# SparkFun_6DoF_LSM6DSV16X.net
KiCad netlist of a schematic drawn in EAGLE
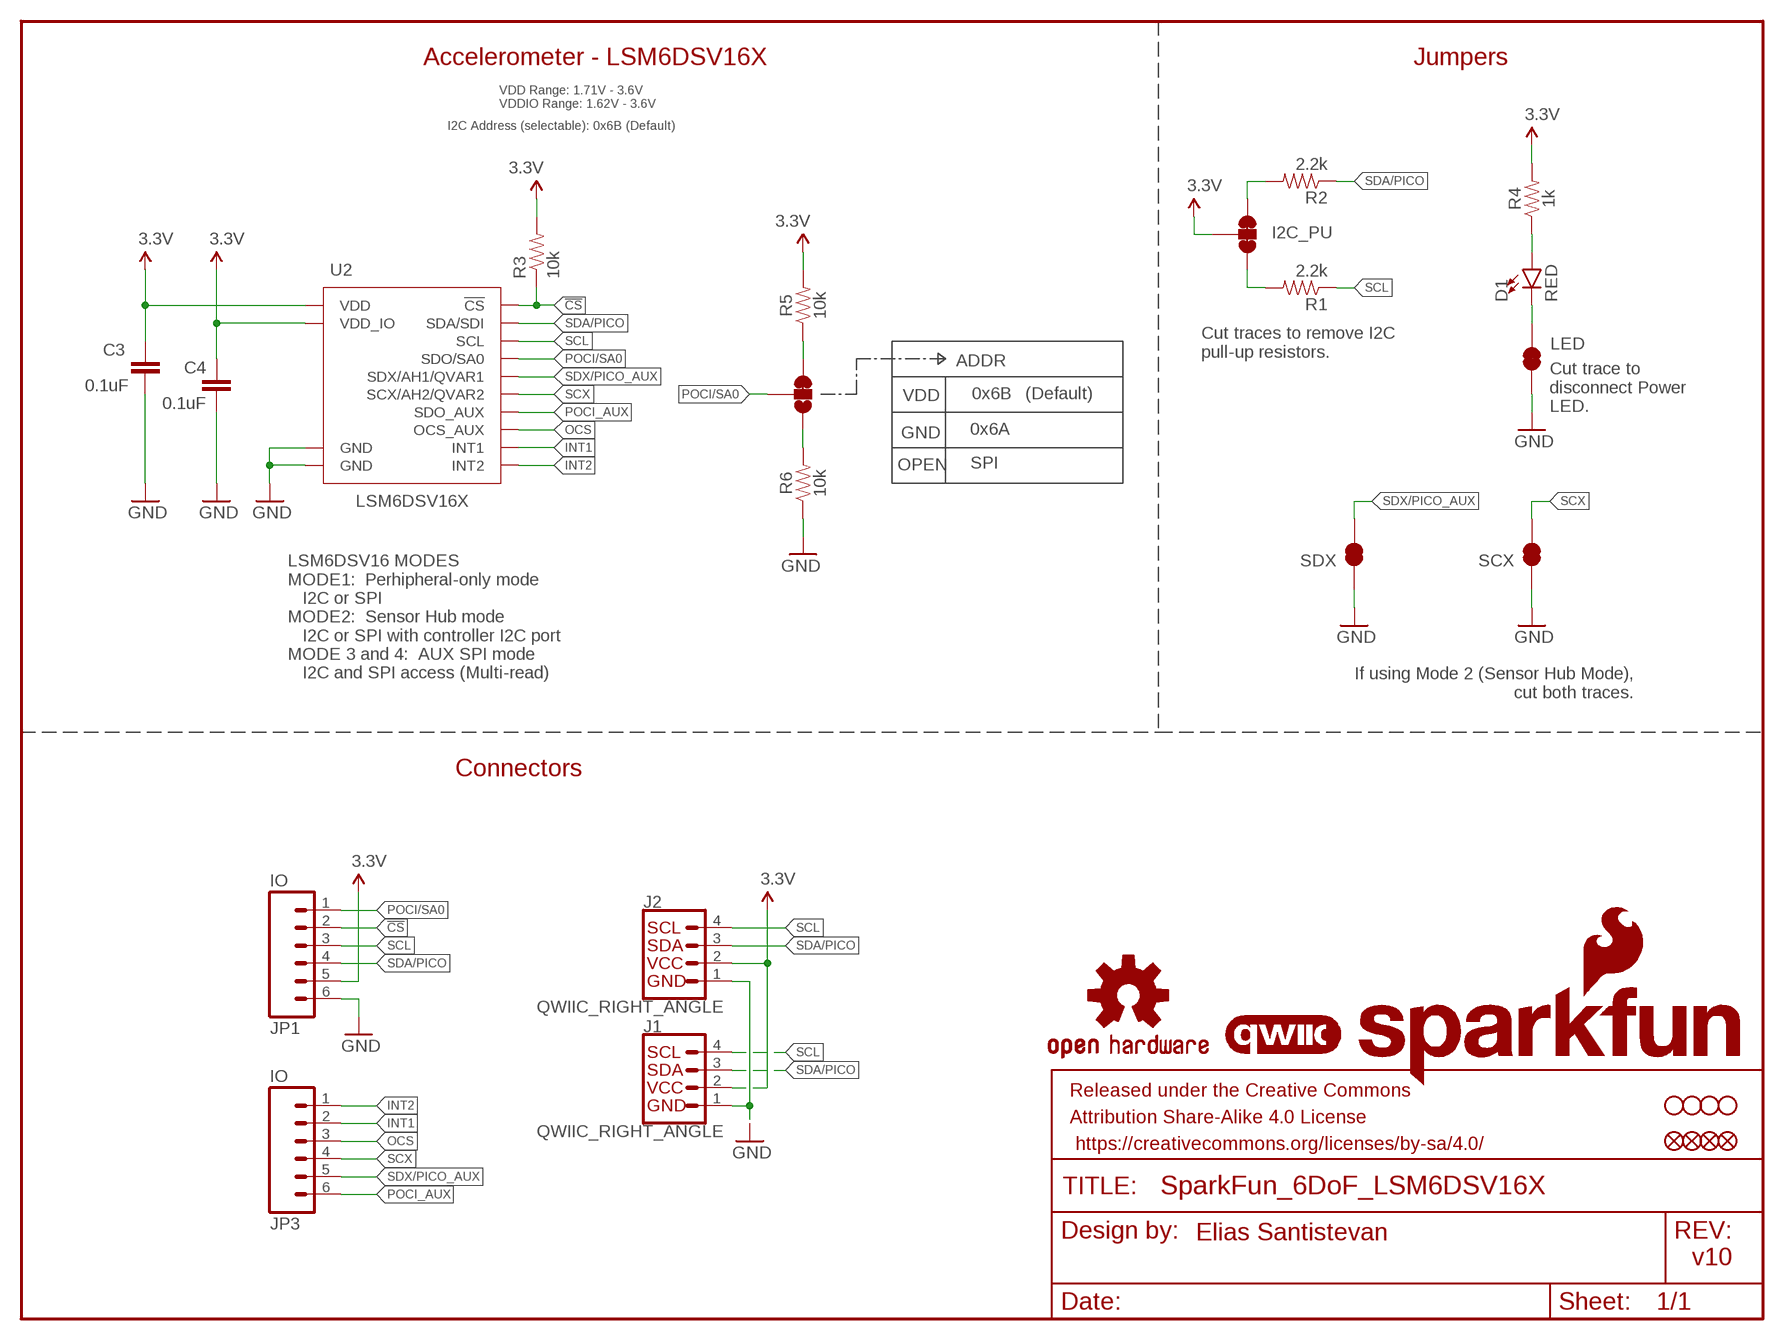
[diagram p0: schematic, sheet 1]

(export (version "E")
  (design (tool "Eeschema 10.0.6"))
  (components
    (comp (ref "ADDR")
      (value "JUMPER-SMT_3_1-NC_TRACE_SILK")
      (footprint "eagle-import:SMT-JUMPER_3_1-NC_TRACE_SILK")
      (libsource (lib "eagle-import") (part "JUMPER-SMT_3_1-NC_TRACE_SILK"))
    )
    (comp (ref "C3")
      (value "0.1uF")
      (footprint "eagle-import:0603")
      (libsource (lib "eagle-import") (part "0.1UF-0603-25V-(+80/-20%)"))
    )
    (comp (ref "C4")
      (value "0.1uF")
      (footprint "eagle-import:0603")
      (libsource (lib "eagle-import") (part "0.1UF-0603-25V-(+80/-20%)"))
    )
    (comp (ref "D1")
      (value "RED")
      (footprint "eagle-import:LED-0603")
      (libsource (lib "eagle-import") (part "LED-RED0603"))
    )
    (comp (ref "FD1")
      (value "FIDUCIALUFIDUCIAL")
      (footprint "eagle-import:FIDUCIAL-MICRO")
      (libsource (lib "eagle-import") (part "FIDUCIALUFIDUCIAL"))
    )
    (comp (ref "FD2")
      (value "FIDUCIALUFIDUCIAL")
      (footprint "eagle-import:FIDUCIAL-MICRO")
      (libsource (lib "eagle-import") (part "FIDUCIALUFIDUCIAL"))
    )
    (comp (ref "FID1")
      (value "FIDUCIALUFIDUCIAL")
      (footprint "eagle-import:FIDUCIAL-MICRO")
      (libsource (lib "eagle-import") (part "FIDUCIALUFIDUCIAL"))
    )
    (comp (ref "FID2")
      (value "FIDUCIALUFIDUCIAL")
      (footprint "eagle-import:FIDUCIAL-MICRO")
      (libsource (lib "eagle-import") (part "FIDUCIALUFIDUCIAL"))
    )
    (comp (ref "FRAME1")
      (value "FRAME-LETTER")
      (footprint "eagle-import:CREATIVE_COMMONS")
      (fields (field (name "DESIGNER") "Elias Santistevan"))
      (libsource (lib "eagle-import") (part "FRAME-LETTER"))
    )
    (comp (ref "I2C_PU")
      (value "S_MODE")
      (footprint "eagle-import:SMT-JUMPER_3_2-NC_TRACE_SILK")
      (libsource (lib "eagle-import") (part "JUMPER-SMT_3_2-NC_TRACE_SILK"))
    )
    (comp (ref "J1")
      (value "QWIIC_RIGHT_ANGLE")
      (footprint "eagle-import:JST04_1MM_RA")
      (libsource (lib "eagle-import") (part "QWIIC_CONNECTORJS-1MM"))
    )
    (comp (ref "J2")
      (value "QWIIC_RIGHT_ANGLE")
      (footprint "eagle-import:JST04_1MM_RA")
      (libsource (lib "eagle-import") (part "QWIIC_CONNECTORJS-1MM"))
    )
    (comp (ref "JP1")
      (value "IO")
      (footprint "eagle-import:1X06_NO_SILK")
      (libsource (lib "eagle-import") (part "CONN_06NO_SILK_NO_POP"))
    )
    (comp (ref "JP3")
      (value "IO")
      (footprint "eagle-import:1X06_NO_SILK")
      (libsource (lib "eagle-import") (part "CONN_06NO_SILK_NO_POP"))
    )
    (comp (ref "LED")
      (value "JUMPER-SMT_2_NC_TRACE_SILK")
      (footprint "eagle-import:SMT-JUMPER_2_NC_TRACE_SILK")
      (libsource (lib "eagle-import") (part "JUMPER-SMT_2_NC_TRACE_SILK"))
    )
    (comp (ref "LOGO1")
      (value "QWIIC_LOGO_4MM")
      (footprint "eagle-import:QWIIC_4MM")
      (libsource (lib "eagle-import") (part "QWIIC_LOGO_4MM"))
    )
    (comp (ref "LOGO2")
      (value "OSHW-LOGOMINI")
      (footprint "eagle-import:OSHW-LOGO-MINI")
      (libsource (lib "eagle-import") (part "OSHW-LOGOMINI"))
    )
    (comp (ref "LOGO3")
      (value "SFE_LOGO_NAME_FLAME.1_INCH")
      (footprint "eagle-import:SFE_LOGO_NAME_FLAME_.1")
      (libsource (lib "eagle-import") (part "SFE_LOGO_NAME_FLAME.1_INCH"))
    )
    (comp (ref "R1")
      (value "2.2k")
      (footprint "eagle-import:0603")
      (libsource (lib "eagle-import") (part "2.2KOHM-0603-1/10W-1%"))
    )
    (comp (ref "R2")
      (value "2.2k")
      (footprint "eagle-import:0603")
      (libsource (lib "eagle-import") (part "2.2KOHM-0603-1/10W-1%"))
    )
    (comp (ref "R3")
      (value "10k")
      (footprint "eagle-import:0603")
      (libsource (lib "eagle-import") (part "10KOHM-0603-1/10W-1%"))
    )
    (comp (ref "R4")
      (value "1k")
      (footprint "eagle-import:0603")
      (libsource (lib "eagle-import") (part "1KOHM-0603-1/10W-1%"))
    )
    (comp (ref "R5")
      (value "10k")
      (footprint "eagle-import:0603")
      (libsource (lib "eagle-import") (part "10KOHM-0603-1/10W-1%"))
    )
    (comp (ref "R6")
      (value "10k")
      (footprint "eagle-import:0603")
      (libsource (lib "eagle-import") (part "10KOHM-0603-1/10W-1%"))
    )
    (comp (ref "SCX")
      (value "JUMPER-SMT_2_NC_TRACE_SILK")
      (footprint "eagle-import:SMT-JUMPER_2_NC_TRACE_SILK")
      (libsource (lib "eagle-import") (part "JUMPER-SMT_2_NC_TRACE_SILK"))
    )
    (comp (ref "SDX")
      (value "JUMPER-SMT_2_NC_TRACE_SILK")
      (footprint "eagle-import:SMT-JUMPER_2_NC_TRACE_SILK")
      (libsource (lib "eagle-import") (part "JUMPER-SMT_2_NC_TRACE_SILK"))
    )
    (comp (ref "STANDOFF1")
      (value "STAND-OFFTIGHT")
      (footprint "eagle-import:STAND-OFF-TIGHT")
      (libsource (lib "eagle-import") (part "STAND-OFFTIGHT"))
    )
    (comp (ref "STANDOFF2")
      (value "STAND-OFFTIGHT")
      (footprint "eagle-import:STAND-OFF-TIGHT")
      (libsource (lib "eagle-import") (part "STAND-OFFTIGHT"))
    )
    (comp (ref "STANDOFF3")
      (value "STAND-OFFTIGHT")
      (footprint "eagle-import:STAND-OFF-TIGHT")
      (libsource (lib "eagle-import") (part "STAND-OFFTIGHT"))
    )
    (comp (ref "STANDOFF4")
      (value "STAND-OFFTIGHT")
      (footprint "eagle-import:STAND-OFF-TIGHT")
      (libsource (lib "eagle-import") (part "STAND-OFFTIGHT"))
    )
    (comp (ref "U2")
      (value "LSM6DSV16X")
      (footprint "eagle-import:LGA-14L")
      (libsource (lib "eagle-import") (part "LSM6DSV16X"))
    )
  )
  (nets
    (net (code "1") (name "/~{CS}") (class "Default")
      (node (ref "JP1") (pin "2") (pinfunction "2_2") (pintype "passive"))
      (node (ref "R3") (pin "1") (pinfunction "1_1") (pintype "passive"))
      (node (ref "U2") (pin "P12") (pinfunction "~{CS}_P12") (pintype "bidirectional"))
    )
    (net (code "2") (name "3.3V") (class "Default")
      (node (ref "C3") (pin "1") (pinfunction "1_1") (pintype "passive"))
      (node (ref "C4") (pin "1") (pinfunction "1_1") (pintype "passive"))
      (node (ref "I2C_PU") (pin "2") (pinfunction "2_2") (pintype "passive"))
      (node (ref "J1") (pin "2") (pinfunction "2_2") (pintype "power_in"))
      (node (ref "J2") (pin "2") (pinfunction "2_2") (pintype "power_in"))
      (node (ref "JP1") (pin "5") (pinfunction "5_5") (pintype "passive"))
      (node (ref "R3") (pin "2") (pinfunction "2_2") (pintype "passive"))
      (node (ref "R4") (pin "2") (pinfunction "2_2") (pintype "passive"))
      (node (ref "R5") (pin "2") (pinfunction "2_2") (pintype "passive"))
      (node (ref "U2") (pin "P5") (pinfunction "VDD_IO_P5") (pintype "power_in"))
      (node (ref "U2") (pin "P8") (pinfunction "VDD_P8") (pintype "power_in"))
    )
    (net (code "3") (name "GND") (class "Default")
      (node (ref "C3") (pin "2") (pinfunction "2_2") (pintype "passive"))
      (node (ref "C4") (pin "2") (pinfunction "2_2") (pintype "passive"))
      (node (ref "J1") (pin "1") (pinfunction "1_1") (pintype "power_in"))
      (node (ref "J2") (pin "1") (pinfunction "1_1") (pintype "power_in"))
      (node (ref "JP1") (pin "6") (pinfunction "6_6") (pintype "passive"))
      (node (ref "LED") (pin "1") (pinfunction "1_1") (pintype "passive"))
      (node (ref "R6") (pin "1") (pinfunction "1_1") (pintype "passive"))
      (node (ref "SCX") (pin "1") (pinfunction "1_1") (pintype "passive"))
      (node (ref "SDX") (pin "1") (pinfunction "1_1") (pintype "passive"))
      (node (ref "U2") (pin "P6") (pinfunction "GND_P6") (pintype "power_in"))
      (node (ref "U2") (pin "P7") (pinfunction "GND_P7") (pintype "power_in"))
    )
    (net (code "4") (name "INT1") (class "Default")
      (node (ref "JP3") (pin "2") (pinfunction "2_2") (pintype "passive"))
      (node (ref "U2") (pin "P4") (pinfunction "INT1_P4") (pintype "bidirectional"))
    )
    (net (code "5") (name "INT2") (class "Default")
      (node (ref "JP3") (pin "1") (pinfunction "1_1") (pintype "passive"))
      (node (ref "U2") (pin "P9") (pinfunction "INT2_P9") (pintype "bidirectional"))
    )
    (net (code "6") (name "Net-(ADDR-Pad1)") (class "Default")
      (node (ref "ADDR") (pin "1") (pinfunction "1_1") (pintype "passive"))
      (node (ref "R6") (pin "2") (pinfunction "2_2") (pintype "passive"))
    )
    (net (code "7") (name "Net-(ADDR-Pad3)") (class "Default")
      (node (ref "ADDR") (pin "3") (pinfunction "3_3") (pintype "passive"))
      (node (ref "R5") (pin "1") (pinfunction "1_1") (pintype "passive"))
    )
    (net (code "8") (name "Net-(D1-PadA)") (class "Default")
      (node (ref "D1") (pin "A") (pinfunction "A_A") (pintype "passive"))
      (node (ref "R4") (pin "1") (pinfunction "1_1") (pintype "passive"))
    )
    (net (code "9") (name "Net-(D1-PadC)") (class "Default")
      (node (ref "D1") (pin "C") (pinfunction "C_C") (pintype "passive"))
      (node (ref "LED") (pin "2") (pinfunction "2_2") (pintype "passive"))
    )
    (net (code "10") (name "Net-(I2C_PU-Pad1)") (class "Default")
      (node (ref "I2C_PU") (pin "1") (pinfunction "1_1") (pintype "passive"))
      (node (ref "R1") (pin "2") (pinfunction "2_2") (pintype "passive"))
    )
    (net (code "11") (name "Net-(I2C_PU-Pad3)") (class "Default")
      (node (ref "I2C_PU") (pin "3") (pinfunction "3_3") (pintype "passive"))
      (node (ref "R2") (pin "2") (pinfunction "2_2") (pintype "passive"))
    )
    (net (code "12") (name "OCS") (class "Default")
      (node (ref "JP3") (pin "3") (pinfunction "3_3") (pintype "passive"))
      (node (ref "U2") (pin "P10") (pinfunction "OCS_AUX_P10") (pintype "bidirectional"))
    )
    (net (code "13") (name "POCI_AUX") (class "Default")
      (node (ref "JP3") (pin "6") (pinfunction "6_6") (pintype "passive"))
      (node (ref "U2") (pin "P11") (pinfunction "SDO_AUX_P11") (pintype "bidirectional"))
    )
    (net (code "14") (name "POCI{slash}SA0") (class "Default")
      (node (ref "ADDR") (pin "2") (pinfunction "2_2") (pintype "passive"))
      (node (ref "JP1") (pin "1") (pinfunction "1_1") (pintype "passive"))
      (node (ref "U2") (pin "P1") (pinfunction "SDO/SA0_P1") (pintype "bidirectional"))
    )
    (net (code "15") (name "SCL") (class "Default")
      (node (ref "J1") (pin "4") (pinfunction "4_4") (pintype "passive"))
      (node (ref "J2") (pin "4") (pinfunction "4_4") (pintype "passive"))
      (node (ref "JP1") (pin "3") (pinfunction "3_3") (pintype "passive"))
      (node (ref "R1") (pin "1") (pinfunction "1_1") (pintype "passive"))
      (node (ref "U2") (pin "P13") (pinfunction "SCL_P13") (pintype "bidirectional"))
    )
    (net (code "16") (name "SCX") (class "Default")
      (node (ref "JP3") (pin "4") (pinfunction "4_4") (pintype "passive"))
      (node (ref "SCX") (pin "2") (pinfunction "2_2") (pintype "passive"))
      (node (ref "U2") (pin "P3") (pinfunction "SCX/AH2/QVAR2_P3") (pintype "bidirectional"))
    )
    (net (code "17") (name "SDA{slash}PICO") (class "Default")
      (node (ref "J1") (pin "3") (pinfunction "3_3") (pintype "passive"))
      (node (ref "J2") (pin "3") (pinfunction "3_3") (pintype "passive"))
      (node (ref "JP1") (pin "4") (pinfunction "4_4") (pintype "passive"))
      (node (ref "R2") (pin "1") (pinfunction "1_1") (pintype "passive"))
      (node (ref "U2") (pin "P14") (pinfunction "SDA/SDI_P14") (pintype "bidirectional"))
    )
    (net (code "18") (name "SDX{slash}PICO_AUX") (class "Default")
      (node (ref "JP3") (pin "5") (pinfunction "5_5") (pintype "passive"))
      (node (ref "SDX") (pin "2") (pinfunction "2_2") (pintype "passive"))
      (node (ref "U2") (pin "P2") (pinfunction "SDX/AH1/QVAR1_P2") (pintype "bidirectional"))
    )
  )
)
